# xl4015.net
KiCad netlist of a schematic drawn in Altium Designer
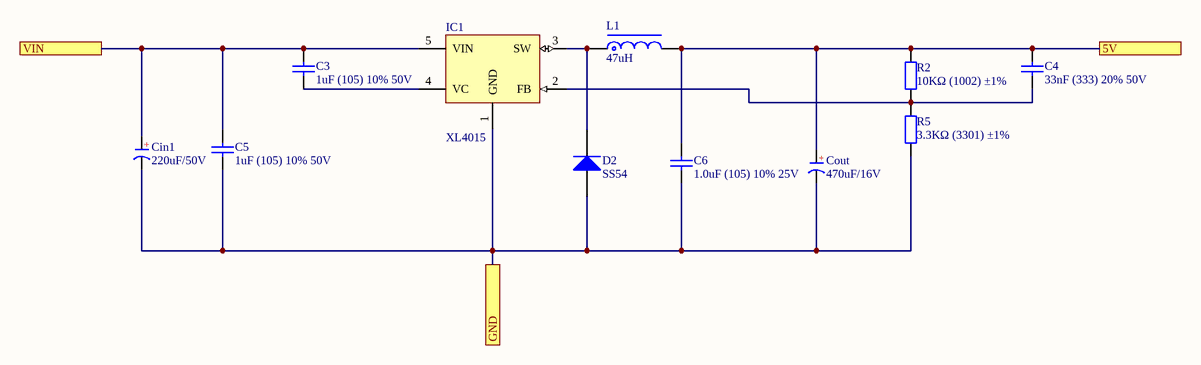
[diagram p0: xl4015.SchDoc]

(export (version "E")
  (design (tool "Eeschema 10.0.6"))
  (components
    (comp (ref "C3")
      (value "1uF (105) 10% 50V")
      (footprint "0603_C")
      (description "贴片电容")
      (libsource (lib "Miscellaneous Devices LC") (part "0603 1uF (105) 10% 50V"))
    )
    (comp (ref "C4")
      (value "33nF (333) 20% 50V")
      (footprint "0402_C")
      (description "贴片电容")
      (libsource (lib "Miscellaneous Devices LC") (part "0402 33nF (333) 20% 50V"))
    )
    (comp (ref "C5")
      (value "1uF (105) 10% 50V")
      (footprint "0603_C")
      (description "贴片电容")
      (libsource (lib "Miscellaneous Devices LC") (part "0603 1uF (105) 10% 50V"))
    )
    (comp (ref "C6")
      (value "1.0uF (105) 10% 25V")
      (footprint "0402_C")
      (description "贴片电容")
      (libsource (lib "Miscellaneous Devices LC") (part "0402 1.0uF (105) 10% 25V"))
    )
    (comp (ref "Cin1")
      (value "220uF/50V")
      (footprint "CM F(10*10.2)")
      (description "贴片电解电容")
      (fields (field (name "版权归属") "源创客"))
      (libsource (lib "3.1   - 电阻-电容-电感") (part "C-CM"))
    )
    (comp (ref "Cout")
      (value "470uF/16V")
      (footprint "CM E(8*10.2)")
      (description "贴片电解电容")
      (fields (field (name "版权归属") "源创客"))
      (libsource (lib "3.1   - 电阻-电容-电感") (part "C-CM"))
    )
    (comp (ref "D2")
      (value "SS54")
      (footprint "SMA(DO-214AC)_S1")
      (description "二极管")
      (libsource (lib "Miscellaneous Devices LC") (part "SMA(DO-214AC) SS54"))
    )
    (comp (ref "IC1")
      (value "XL4015")
      (footprint "TO263-5A")
      (description "DC降压芯片")
      (fields (field (name "版权归属") "源创客"))
      (libsource (lib "1.3   - 电源类芯片") (part "XL4015"))
    )
    (comp (ref "L1")
      (value "47uH")
      (footprint "CDRH127")
      (description "功率屏蔽电感")
      (fields (field (name "版权归属") "源创客"))
      (libsource (lib "3.1   - 电阻-电容-电感") (part "L-CDRH"))
    )
    (comp (ref "R2")
      (value "10KΩ (1002) ±1%")
      (footprint "0603_R")
      (description "贴片电阻")
      (libsource (lib "Miscellaneous Devices LC") (part "0603 10KΩ (1002) 1%"))
    )
    (comp (ref "R5")
      (value "3.3KΩ (3301) ±1%")
      (footprint "0603_R")
      (description "贴片电阻")
      (libsource (lib "Miscellaneous Devices LC") (part "0603 3.3KΩ (3301) 1%"))
    )
  )
  (nets
    (net (code "1") (name "/5V") (class "Default")
      (node (ref "C4") (pin "2") (pinfunction "2_2") (pintype "passive"))
      (node (ref "C6") (pin "2") (pinfunction "2_2") (pintype "passive"))
      (node (ref "Cout") (pin "1") (pinfunction "A_1") (pintype "passive"))
      (node (ref "L1") (pin "2") (pinfunction "2_2") (pintype "passive"))
      (node (ref "R2") (pin "2") (pinfunction "2_2") (pintype "passive"))
    )
    (net (code "2") (name "/GND") (class "Default")
      (node (ref "C5") (pin "1") (pinfunction "1_1") (pintype "passive"))
      (node (ref "C6") (pin "1") (pinfunction "1_1") (pintype "passive"))
      (node (ref "Cin1") (pin "2") (pinfunction "K_2") (pintype "passive"))
      (node (ref "Cout") (pin "2") (pinfunction "K_2") (pintype "passive"))
      (node (ref "D2") (pin "1") (pinfunction "A_1") (pintype "passive"))
      (node (ref "IC1") (pin "1") (pinfunction "GND_1") (pintype "power_in"))
      (node (ref "R5") (pin "1") (pinfunction "1_1") (pintype "passive"))
    )
    (net (code "3") (name "/VIN") (class "Default")
      (node (ref "C3") (pin "2") (pinfunction "2_2") (pintype "passive"))
      (node (ref "C5") (pin "2") (pinfunction "2_2") (pintype "passive"))
      (node (ref "Cin1") (pin "1") (pinfunction "A_1") (pintype "passive"))
      (node (ref "IC1") (pin "5") (pinfunction "VIN_5") (pintype "power_in"))
    )
    (net (code "4") (name "Net-(D2-K)") (class "Default")
      (node (ref "D2") (pin "2") (pinfunction "K_2") (pintype "passive"))
      (node (ref "IC1") (pin "3") (pinfunction "SW_3") (pintype "bidirectional"))
      (node (ref "L1") (pin "1") (pinfunction "1_1") (pintype "passive"))
    )
    (net (code "5") (name "Net-(IC1-FB)") (class "Default")
      (node (ref "C4") (pin "1") (pinfunction "1_1") (pintype "passive"))
      (node (ref "IC1") (pin "2") (pinfunction "FB_2") (pintype "input"))
      (node (ref "R2") (pin "1") (pinfunction "1_1") (pintype "passive"))
      (node (ref "R5") (pin "2") (pinfunction "2_2") (pintype "passive"))
    )
    (net (code "6") (name "Net-(IC1-VC)") (class "Default")
      (node (ref "C3") (pin "1") (pinfunction "1_1") (pintype "passive"))
      (node (ref "IC1") (pin "4") (pinfunction "VC_4") (pintype "passive"))
    )
  )
)
